# i2c-level-shifter.net
KiCad netlist of a schematic drawn in EAGLE
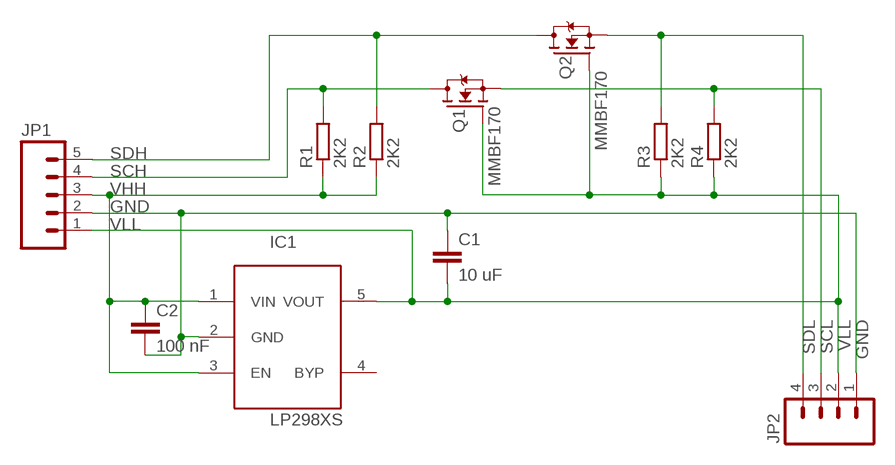
[diagram p0: schematic, sheet 1]

(export (version "E")
  (design (tool "Eeschema 10.0.6"))
  (components
    (comp (ref "C1")
      (value "10 uF")
      (footprint "eagle-import:C1206")
      (libsource (lib "eagle-import") (part "C-EUC1206"))
    )
    (comp (ref "C2")
      (value "100 nF")
      (footprint "eagle-import:C0805")
      (libsource (lib "eagle-import") (part "C-EUC0805"))
    )
    (comp (ref "IC1")
      (value "LP298XS")
      (footprint "eagle-import:SOT23-5L")
      (libsource (lib "eagle-import") (part "LP298XS"))
    )
    (comp (ref "JP1")
      (value "M05PTH")
      (footprint "eagle-import:1X05")
      (libsource (lib "eagle-import") (part "M05PTH"))
    )
    (comp (ref "JP2")
      (value "M04PTH")
      (footprint "eagle-import:1X04")
      (libsource (lib "eagle-import") (part "M04PTH"))
    )
    (comp (ref "Q1")
      (value "MMBF170")
      (footprint "eagle-import:SOT-23")
      (libsource (lib "eagle-import") (part "TRANSISTOR_FET_BS170-SOT-23"))
    )
    (comp (ref "Q2")
      (value "MMBF170")
      (footprint "eagle-import:SOT-23")
      (libsource (lib "eagle-import") (part "TRANSISTOR_FET_BS170-SOT-23"))
    )
    (comp (ref "R1")
      (value "2K2")
      (footprint "eagle-import:R0603")
      (libsource (lib "eagle-import") (part "R-EU_R0603"))
    )
    (comp (ref "R2")
      (value "2K2")
      (footprint "eagle-import:R0603")
      (libsource (lib "eagle-import") (part "R-EU_R0603"))
    )
    (comp (ref "R3")
      (value "2K2")
      (footprint "eagle-import:R0603")
      (libsource (lib "eagle-import") (part "R-EU_R0603"))
    )
    (comp (ref "R4")
      (value "2K2")
      (footprint "eagle-import:R0603")
      (libsource (lib "eagle-import") (part "R-EU_R0603"))
    )
  )
  (nets
    (net (code "1") (name "/GND") (class "Default")
      (node (ref "C1") (pin "1") (pinfunction "1_1") (pintype "passive"))
      (node (ref "C2") (pin "2") (pinfunction "2_2") (pintype "passive"))
      (node (ref "IC1") (pin "2") (pinfunction "GND_2") (pintype "bidirectional"))
      (node (ref "JP1") (pin "2") (pinfunction "2_2") (pintype "passive"))
      (node (ref "JP2") (pin "1") (pinfunction "1_1") (pintype "passive"))
    )
    (net (code "2") (name "/SCH") (class "Default")
      (node (ref "JP1") (pin "4") (pinfunction "4_4") (pintype "passive"))
      (node (ref "Q1") (pin "3") (pinfunction "D_3") (pintype "passive"))
      (node (ref "R1") (pin "2") (pinfunction "2_2") (pintype "passive"))
    )
    (net (code "3") (name "/SCL") (class "Default")
      (node (ref "JP2") (pin "4") (pinfunction "4_4") (pintype "passive"))
      (node (ref "Q2") (pin "2") (pinfunction "S_2") (pintype "passive"))
      (node (ref "R3") (pin "2") (pinfunction "2_2") (pintype "passive"))
    )
    (net (code "4") (name "/SDH") (class "Default")
      (node (ref "JP1") (pin "5") (pinfunction "5_5") (pintype "passive"))
      (node (ref "Q2") (pin "3") (pinfunction "D_3") (pintype "passive"))
      (node (ref "R2") (pin "2") (pinfunction "2_2") (pintype "passive"))
    )
    (net (code "5") (name "/SDL") (class "Default")
      (node (ref "JP2") (pin "3") (pinfunction "3_3") (pintype "passive"))
      (node (ref "Q1") (pin "2") (pinfunction "S_2") (pintype "passive"))
      (node (ref "R4") (pin "2") (pinfunction "2_2") (pintype "passive"))
    )
    (net (code "6") (name "/VHH") (class "Default")
      (node (ref "C2") (pin "1") (pinfunction "1_1") (pintype "passive"))
      (node (ref "IC1") (pin "1") (pinfunction "VIN_1") (pintype "bidirectional"))
      (node (ref "IC1") (pin "3") (pinfunction "EN_3") (pintype "bidirectional"))
      (node (ref "JP1") (pin "3") (pinfunction "3_3") (pintype "passive"))
      (node (ref "R1") (pin "1") (pinfunction "1_1") (pintype "passive"))
      (node (ref "R2") (pin "1") (pinfunction "1_1") (pintype "passive"))
    )
    (net (code "7") (name "/VLL") (class "Default")
      (node (ref "C1") (pin "2") (pinfunction "2_2") (pintype "passive"))
      (node (ref "IC1") (pin "5") (pinfunction "VOUT_5") (pintype "bidirectional"))
      (node (ref "JP1") (pin "1") (pinfunction "1_1") (pintype "passive"))
      (node (ref "JP2") (pin "2") (pinfunction "2_2") (pintype "passive"))
      (node (ref "Q1") (pin "1") (pinfunction "G_1") (pintype "passive"))
      (node (ref "Q2") (pin "1") (pinfunction "G_1") (pintype "passive"))
      (node (ref "R3") (pin "1") (pinfunction "1_1") (pintype "passive"))
      (node (ref "R4") (pin "1") (pinfunction "1_1") (pintype "passive"))
    )
    (net (code "8") (name "unconnected-(IC1-BYP-Pad4)") (class "Default")
      (node (ref "IC1") (pin "4") (pinfunction "BYP_4") (pintype "bidirectional"))
    )
  )
)
